# tps62130.net
KiCad netlist of a schematic drawn in Altium Designer
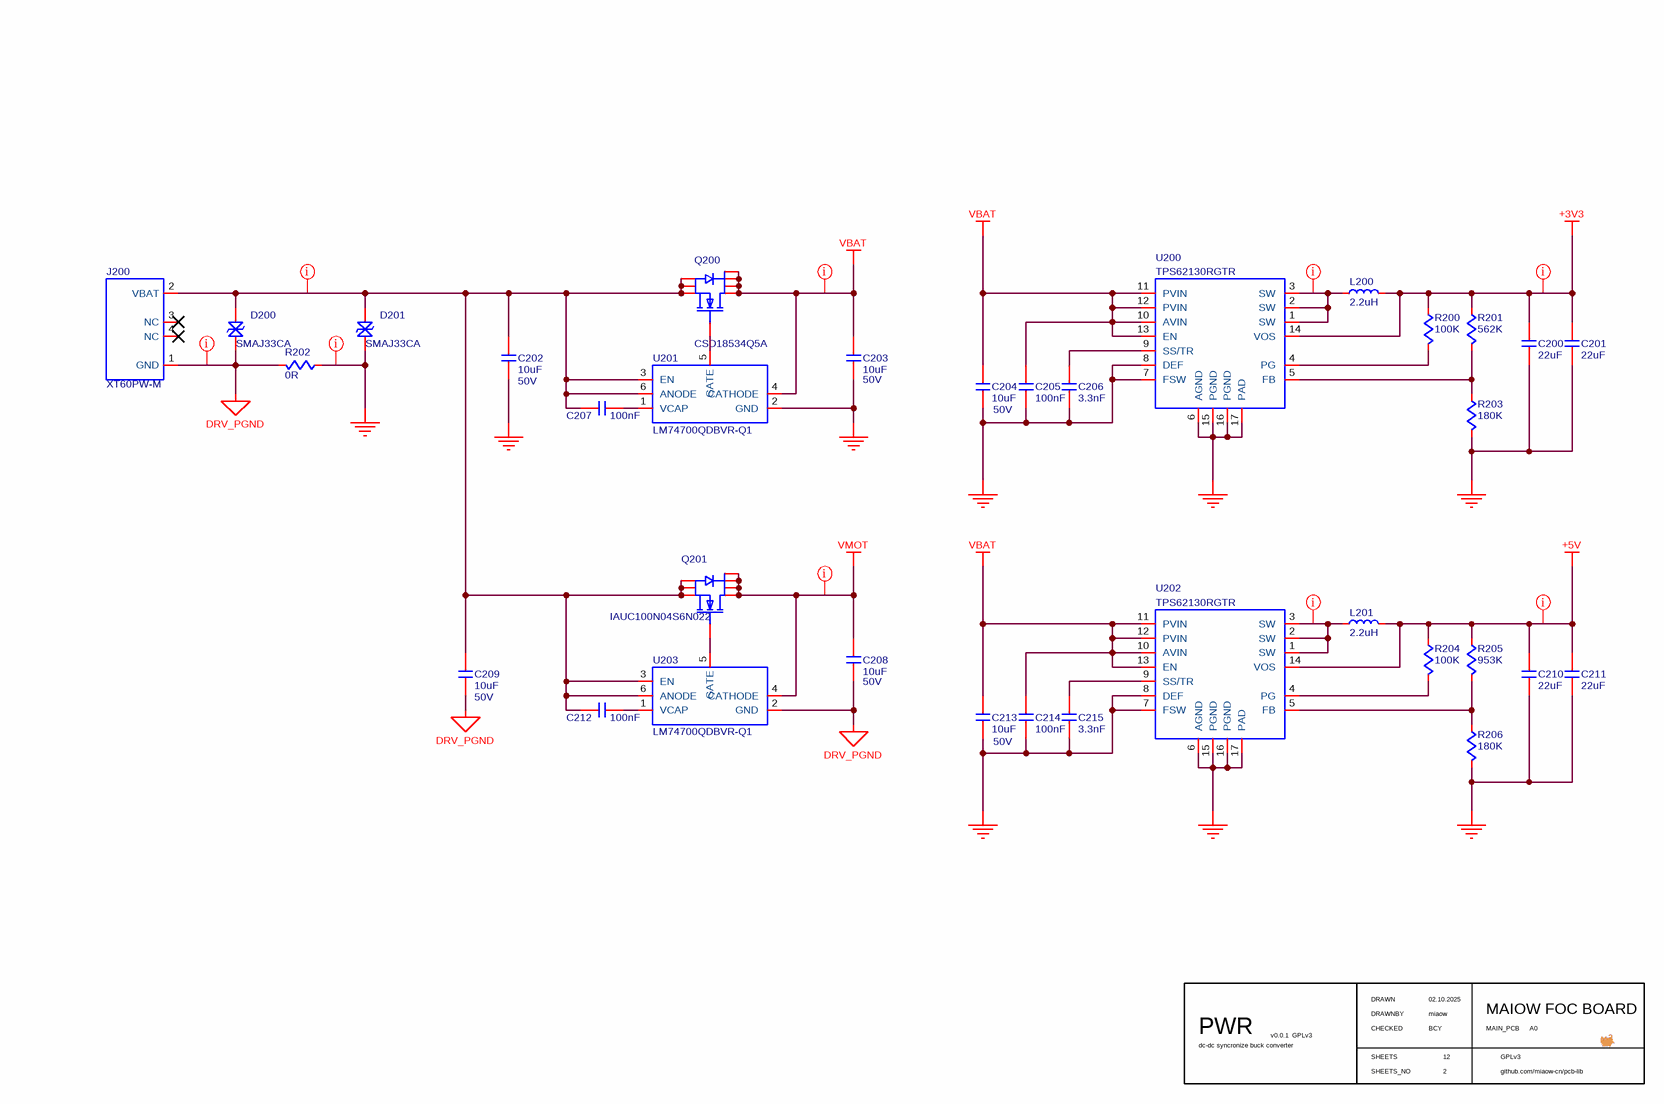
[diagram p0: tps62130.SchDoc]

(export (version "E")
  (design (tool "Eeschema 10.0.6"))
  (components
    (comp (ref "C200")
      (value "22uF")
      (footprint "mw:C0805")
      (fields (field (name "VOLTAGE") "25V") (field (name "Comment") "C-NOMO"))
      (libsource (lib "mw") (part "C-NOMO"))
    )
    (comp (ref "C201")
      (value "22uF")
      (footprint "mw:C0805")
      (fields (field (name "VOLTAGE") "25V") (field (name "Comment") "C-NOMO"))
      (libsource (lib "mw") (part "C-NOMO"))
    )
    (comp (ref "C202")
      (value "10uF")
      (footprint "mw:C0805")
      (fields (field (name "VOLTAGE") "50V") (field (name "Comment") "C-NOMO"))
      (libsource (lib "mw") (part "C-NOMO"))
    )
    (comp (ref "C203")
      (value "10uF")
      (footprint "mw:C0805")
      (fields (field (name "VOLTAGE") "50V") (field (name "Comment") "C-NOMO"))
      (libsource (lib "mw") (part "C-NOMO"))
    )
    (comp (ref "C204")
      (value "10uF")
      (footprint "mw:C0805")
      (fields (field (name "VOLTAGE") "50V") (field (name "Comment") "C-NOMO"))
      (libsource (lib "mw") (part "C-NOMO"))
    )
    (comp (ref "C205")
      (value "100nF")
      (footprint "mw:C0603")
      (fields (field (name "VOLTAGE") "25V") (field (name "Comment") "C-NOMO"))
      (libsource (lib "mw") (part "C-NOMO"))
    )
    (comp (ref "C206")
      (value "3.3nF")
      (footprint "mw:C0402")
      (fields (field (name "VOLTAGE") "25V") (field (name "Comment") "C-NOMO"))
      (libsource (lib "mw") (part "C-NOMO"))
    )
    (comp (ref "C207")
      (value "100nF")
      (footprint "mw:C0402")
      (fields (field (name "VOLTAGE") "25V") (field (name "Comment") "C-NOMO"))
      (libsource (lib "mw") (part "C-NOMO"))
    )
    (comp (ref "C208")
      (value "10uF")
      (footprint "mw:C0805")
      (fields (field (name "VOLTAGE") "50V") (field (name "Comment") "C-NOMO"))
      (libsource (lib "mw") (part "C-NOMO"))
    )
    (comp (ref "C209")
      (value "10uF")
      (footprint "mw:C0805")
      (fields (field (name "VOLTAGE") "50V") (field (name "Comment") "C-NOMO"))
      (libsource (lib "mw") (part "C-NOMO"))
    )
    (comp (ref "C210")
      (value "22uF")
      (footprint "mw:C0805")
      (fields (field (name "VOLTAGE") "25V") (field (name "Comment") "C-NOMO"))
      (libsource (lib "mw") (part "C-NOMO"))
    )
    (comp (ref "C211")
      (value "22uF")
      (footprint "mw:C0805")
      (fields (field (name "VOLTAGE") "25V") (field (name "Comment") "C-NOMO"))
      (libsource (lib "mw") (part "C-NOMO"))
    )
    (comp (ref "C212")
      (value "100nF")
      (footprint "mw:C0402")
      (fields (field (name "VOLTAGE") "25V") (field (name "Comment") "C-NOMO"))
      (libsource (lib "mw") (part "C-NOMO"))
    )
    (comp (ref "C213")
      (value "10uF")
      (footprint "mw:C0805")
      (fields (field (name "VOLTAGE") "50V") (field (name "Comment") "C-NOMO"))
      (libsource (lib "mw") (part "C-NOMO"))
    )
    (comp (ref "C214")
      (value "100nF")
      (footprint "mw:C0603")
      (fields (field (name "VOLTAGE") "25V") (field (name "Comment") "C-NOMO"))
      (libsource (lib "mw") (part "C-NOMO"))
    )
    (comp (ref "C215")
      (value "3.3nF")
      (footprint "mw:C0402")
      (fields (field (name "VOLTAGE") "25V") (field (name "Comment") "C-NOMO"))
      (libsource (lib "mw") (part "C-NOMO"))
    )
    (comp (ref "D200")
      (value "SMAJ33CA")
      (footprint "mw:SMAJ33CA")
      (description "TVS/ESD")
      (libsource (lib "mw") (part "SMAJ33CA"))
    )
    (comp (ref "D201")
      (value "SMAJ33CA")
      (footprint "mw:SMAJ33CA")
      (description "TVS/ESD")
      (libsource (lib "mw") (part "SMAJ33CA"))
    )
    (comp (ref "J200")
      (value "XT60PW-M")
      (footprint "mw:XT60PW-M")
      (description "CONNECTOR - dc supply")
      (libsource (lib "mw") (part "XT60PW-M"))
    )
    (comp (ref "L200")
      (value "2.2uH")
      (footprint "mw:FXL0420")
      (fields (field (name "Comment") "L") (field (name "PUBLISHER") "Altium Limited"))
      (libsource (lib "mw") (part "L"))
    )
    (comp (ref "L201")
      (value "2.2uH")
      (footprint "mw:FXL0420")
      (fields (field (name "Comment") "L") (field (name "PUBLISHER") "Altium Limited"))
      (libsource (lib "mw") (part "L"))
    )
    (comp (ref "Q200")
      (value "CSD18534Q5A")
      (footprint "mw:CSD18534Q5A")
      (description "NMOS")
      (libsource (lib "mw") (part "CSD18534Q5A"))
    )
    (comp (ref "Q201")
      (value "IAUC100N04S6N022")
      (footprint "mw:IAUC100N04S6N022")
      (description "NMOS")
      (libsource (lib "mw") (part "IAUC100N04S6N022"))
    )
    (comp (ref "R200")
      (value "100K")
      (footprint "mw:R0402")
      (fields (field (name "Comment") "R"))
      (libsource (lib "mw") (part "R"))
    )
    (comp (ref "R201")
      (value "562K")
      (footprint "mw:R0603")
      (fields (field (name "Comment") "R"))
      (libsource (lib "mw") (part "R"))
    )
    (comp (ref "R202")
      (value "0R")
      (footprint "mw:R1206")
      (fields (field (name "Comment") "R"))
      (libsource (lib "mw") (part "R"))
    )
    (comp (ref "R203")
      (value "180K")
      (footprint "mw:R0603")
      (fields (field (name "Comment") "R"))
      (libsource (lib "mw") (part "R"))
    )
    (comp (ref "R204")
      (value "100K")
      (footprint "mw:R0402")
      (fields (field (name "Comment") "R"))
      (libsource (lib "mw") (part "R"))
    )
    (comp (ref "R205")
      (value "953K")
      (footprint "mw:R0603")
      (fields (field (name "Comment") "R"))
      (libsource (lib "mw") (part "R"))
    )
    (comp (ref "R206")
      (value "180K")
      (footprint "mw:R0603")
      (fields (field (name "Comment") "R"))
      (libsource (lib "mw") (part "R"))
    )
    (comp (ref "U200")
      (value "TPS62130RGTR")
      (footprint "mw:TPS62130RGTR")
      (libsource (lib "mw") (part "TPS62130RGTR"))
    )
    (comp (ref "U201")
      (value "LM74700QDBVR-Q1")
      (footprint "mw:LM74700QDBVR-Q1")
      (description "IDEAL DIODE")
      (libsource (lib "mw") (part "LM74700QDBVR-Q1"))
    )
    (comp (ref "U202")
      (value "TPS62130RGTR")
      (footprint "mw:TPS62130RGTR")
      (libsource (lib "mw") (part "TPS62130RGTR"))
    )
    (comp (ref "U203")
      (value "LM74700QDBVR-Q1")
      (footprint "mw:LM74700QDBVR-Q1")
      (description "IDEAL DIODE")
      (libsource (lib "mw") (part "LM74700QDBVR-Q1"))
    )
  )
  (nets
    (net (code "1") (name "+3V3") (class "Default")
      (node (ref "C200") (pin "2") (pinfunction "2_2") (pintype "passive"))
      (node (ref "C201") (pin "2") (pinfunction "2_2") (pintype "passive"))
      (node (ref "L200") (pin "2") (pinfunction "2_2") (pintype "passive"))
      (node (ref "R200") (pin "2") (pinfunction "2_2") (pintype "passive"))
      (node (ref "R201") (pin "2") (pinfunction "2_2") (pintype "passive"))
      (node (ref "U200") (pin "14") (pinfunction "VOS_14") (pintype "passive"))
    )
    (net (code "2") (name "+5V") (class "Default")
      (node (ref "C210") (pin "2") (pinfunction "2_2") (pintype "passive"))
      (node (ref "C211") (pin "2") (pinfunction "2_2") (pintype "passive"))
      (node (ref "L201") (pin "2") (pinfunction "2_2") (pintype "passive"))
      (node (ref "R204") (pin "2") (pinfunction "2_2") (pintype "passive"))
      (node (ref "R205") (pin "2") (pinfunction "2_2") (pintype "passive"))
      (node (ref "U202") (pin "14") (pinfunction "VOS_14") (pintype "passive"))
    )
    (net (code "3") (name "DRV_PGND") (class "Default")
      (node (ref "C208") (pin "1") (pinfunction "1_1") (pintype "passive"))
      (node (ref "C209") (pin "1") (pinfunction "1_1") (pintype "passive"))
      (node (ref "D200") (pin "1") (pinfunction "1_1") (pintype "passive"))
      (node (ref "J200") (pin "1") (pinfunction "GND_1") (pintype "passive"))
      (node (ref "R202") (pin "1") (pinfunction "1_1") (pintype "passive"))
      (node (ref "U203") (pin "2") (pinfunction "GND_2") (pintype "passive"))
    )
    (net (code "4") (name "GND") (class "Default")
      (node (ref "C200") (pin "1") (pinfunction "1_1") (pintype "passive"))
      (node (ref "C201") (pin "1") (pinfunction "1_1") (pintype "passive"))
      (node (ref "C202") (pin "1") (pinfunction "1_1") (pintype "passive"))
      (node (ref "C203") (pin "1") (pinfunction "1_1") (pintype "passive"))
      (node (ref "C204") (pin "1") (pinfunction "1_1") (pintype "passive"))
      (node (ref "C205") (pin "1") (pinfunction "1_1") (pintype "passive"))
      (node (ref "C206") (pin "1") (pinfunction "1_1") (pintype "passive"))
      (node (ref "C210") (pin "1") (pinfunction "1_1") (pintype "passive"))
      (node (ref "C211") (pin "1") (pinfunction "1_1") (pintype "passive"))
      (node (ref "C213") (pin "1") (pinfunction "1_1") (pintype "passive"))
      (node (ref "C214") (pin "1") (pinfunction "1_1") (pintype "passive"))
      (node (ref "C215") (pin "1") (pinfunction "1_1") (pintype "passive"))
      (node (ref "D201") (pin "1") (pinfunction "1_1") (pintype "passive"))
      (node (ref "R202") (pin "2") (pinfunction "2_2") (pintype "passive"))
      (node (ref "R203") (pin "1") (pinfunction "1_1") (pintype "passive"))
      (node (ref "R206") (pin "1") (pinfunction "1_1") (pintype "passive"))
      (node (ref "U200") (pin "15") (pinfunction "PGND_15") (pintype "passive"))
      (node (ref "U200") (pin "16") (pinfunction "PGND_16") (pintype "passive"))
      (node (ref "U200") (pin "17") (pinfunction "PAD_17") (pintype "passive"))
      (node (ref "U200") (pin "6") (pinfunction "AGND_6") (pintype "passive"))
      (node (ref "U200") (pin "7") (pinfunction "FSW_7") (pintype "passive"))
      (node (ref "U200") (pin "8") (pinfunction "DEF_8") (pintype "passive"))
      (node (ref "U201") (pin "2") (pinfunction "GND_2") (pintype "passive"))
      (node (ref "U202") (pin "15") (pinfunction "PGND_15") (pintype "passive"))
      (node (ref "U202") (pin "16") (pinfunction "PGND_16") (pintype "passive"))
      (node (ref "U202") (pin "17") (pinfunction "PAD_17") (pintype "passive"))
      (node (ref "U202") (pin "6") (pinfunction "AGND_6") (pintype "passive"))
      (node (ref "U202") (pin "7") (pinfunction "FSW_7") (pintype "passive"))
      (node (ref "U202") (pin "8") (pinfunction "DEF_8") (pintype "passive"))
    )
    (net (code "5") (name "Net-(J200-VBAT)") (class "Default")
      (node (ref "C202") (pin "2") (pinfunction "2_2") (pintype "passive"))
      (node (ref "C207") (pin "1") (pinfunction "1_1") (pintype "passive"))
      (node (ref "C209") (pin "2") (pinfunction "2_2") (pintype "passive"))
      (node (ref "C212") (pin "1") (pinfunction "1_1") (pintype "passive"))
      (node (ref "D200") (pin "2") (pinfunction "2_2") (pintype "passive"))
      (node (ref "D201") (pin "2") (pinfunction "2_2") (pintype "passive"))
      (node (ref "J200") (pin "2") (pinfunction "VBAT_2") (pintype "passive"))
      (node (ref "Q200") (pin "1") (pinfunction "S_1") (pintype "passive"))
      (node (ref "Q200") (pin "2") (pinfunction "S_2") (pintype "passive"))
      (node (ref "Q200") (pin "3") (pinfunction "S_3") (pintype "passive"))
      (node (ref "Q201") (pin "1") (pinfunction "S_1") (pintype "passive"))
      (node (ref "Q201") (pin "2") (pinfunction "S_2") (pintype "passive"))
      (node (ref "Q201") (pin "3") (pinfunction "S_3") (pintype "passive"))
      (node (ref "U201") (pin "3") (pinfunction "EN_3") (pintype "passive"))
      (node (ref "U201") (pin "6") (pinfunction "ANODE_6") (pintype "passive"))
      (node (ref "U203") (pin "3") (pinfunction "EN_3") (pintype "passive"))
      (node (ref "U203") (pin "6") (pinfunction "ANODE_6") (pintype "passive"))
    )
    (net (code "6") (name "Net-(L200-Pad1)") (class "Default")
      (node (ref "L200") (pin "1") (pinfunction "1_1") (pintype "passive"))
      (node (ref "U200") (pin "1") (pinfunction "SW_1") (pintype "passive"))
      (node (ref "U200") (pin "2") (pinfunction "SW_2") (pintype "passive"))
      (node (ref "U200") (pin "3") (pinfunction "SW_3") (pintype "passive"))
    )
    (net (code "7") (name "Net-(L201-Pad1)") (class "Default")
      (node (ref "L201") (pin "1") (pinfunction "1_1") (pintype "passive"))
      (node (ref "U202") (pin "1") (pinfunction "SW_1") (pintype "passive"))
      (node (ref "U202") (pin "2") (pinfunction "SW_2") (pintype "passive"))
      (node (ref "U202") (pin "3") (pinfunction "SW_3") (pintype "passive"))
    )
    (net (code "8") (name "Net-(Q200-G)") (class "Default")
      (node (ref "Q200") (pin "4") (pinfunction "G_4") (pintype "passive"))
      (node (ref "U201") (pin "5") (pinfunction "GATE_5") (pintype "passive"))
    )
    (net (code "9") (name "Net-(Q201-G)") (class "Default")
      (node (ref "Q201") (pin "4") (pinfunction "G_4") (pintype "passive"))
      (node (ref "U203") (pin "5") (pinfunction "GATE_5") (pintype "passive"))
    )
    (net (code "10") (name "Net-(U200-FB)") (class "Default")
      (node (ref "R201") (pin "1") (pinfunction "1_1") (pintype "passive"))
      (node (ref "R203") (pin "2") (pinfunction "2_2") (pintype "passive"))
      (node (ref "U200") (pin "5") (pinfunction "FB_5") (pintype "passive"))
    )
    (net (code "11") (name "Net-(U200-PG)") (class "Default")
      (node (ref "R200") (pin "1") (pinfunction "1_1") (pintype "passive"))
      (node (ref "U200") (pin "4") (pinfunction "PG_4") (pintype "passive"))
    )
    (net (code "12") (name "Net-(U200-SS{slash}TR)") (class "Default")
      (node (ref "C206") (pin "2") (pinfunction "2_2") (pintype "passive"))
      (node (ref "U200") (pin "9") (pinfunction "SS/TR_9") (pintype "passive"))
    )
    (net (code "13") (name "Net-(U201-VCAP)") (class "Default")
      (node (ref "C207") (pin "2") (pinfunction "2_2") (pintype "passive"))
      (node (ref "U201") (pin "1") (pinfunction "VCAP_1") (pintype "passive"))
    )
    (net (code "14") (name "Net-(U202-FB)") (class "Default")
      (node (ref "R205") (pin "1") (pinfunction "1_1") (pintype "passive"))
      (node (ref "R206") (pin "2") (pinfunction "2_2") (pintype "passive"))
      (node (ref "U202") (pin "5") (pinfunction "FB_5") (pintype "passive"))
    )
    (net (code "15") (name "Net-(U202-PG)") (class "Default")
      (node (ref "R204") (pin "1") (pinfunction "1_1") (pintype "passive"))
      (node (ref "U202") (pin "4") (pinfunction "PG_4") (pintype "passive"))
    )
    (net (code "16") (name "Net-(U202-SS{slash}TR)") (class "Default")
      (node (ref "C215") (pin "2") (pinfunction "2_2") (pintype "passive"))
      (node (ref "U202") (pin "9") (pinfunction "SS/TR_9") (pintype "passive"))
    )
    (net (code "17") (name "Net-(U203-VCAP)") (class "Default")
      (node (ref "C212") (pin "2") (pinfunction "2_2") (pintype "passive"))
      (node (ref "U203") (pin "1") (pinfunction "VCAP_1") (pintype "passive"))
    )
    (net (code "18") (name "VBAT") (class "Default")
      (node (ref "C203") (pin "2") (pinfunction "2_2") (pintype "passive"))
      (node (ref "C204") (pin "2") (pinfunction "2_2") (pintype "passive"))
      (node (ref "C205") (pin "2") (pinfunction "2_2") (pintype "passive"))
      (node (ref "C213") (pin "2") (pinfunction "2_2") (pintype "passive"))
      (node (ref "C214") (pin "2") (pinfunction "2_2") (pintype "passive"))
      (node (ref "Q200") (pin "5") (pinfunction "D_5") (pintype "passive"))
      (node (ref "Q200") (pin "6") (pinfunction "D_6") (pintype "passive"))
      (node (ref "Q200") (pin "7") (pinfunction "D_7") (pintype "passive"))
      (node (ref "Q200") (pin "8") (pinfunction "D_8") (pintype "passive"))
      (node (ref "U200") (pin "10") (pinfunction "AVIN_10") (pintype "passive"))
      (node (ref "U200") (pin "11") (pinfunction "PVIN_11") (pintype "passive"))
      (node (ref "U200") (pin "12") (pinfunction "PVIN_12") (pintype "passive"))
      (node (ref "U200") (pin "13") (pinfunction "EN_13") (pintype "passive"))
      (node (ref "U201") (pin "4") (pinfunction "CATHODE_4") (pintype "passive"))
      (node (ref "U202") (pin "10") (pinfunction "AVIN_10") (pintype "passive"))
      (node (ref "U202") (pin "11") (pinfunction "PVIN_11") (pintype "passive"))
      (node (ref "U202") (pin "12") (pinfunction "PVIN_12") (pintype "passive"))
      (node (ref "U202") (pin "13") (pinfunction "EN_13") (pintype "passive"))
    )
    (net (code "19") (name "VMOT") (class "Default")
      (node (ref "C208") (pin "2") (pinfunction "2_2") (pintype "passive"))
      (node (ref "Q201") (pin "5") (pinfunction "D_5") (pintype "passive"))
      (node (ref "Q201") (pin "6") (pinfunction "D_6") (pintype "passive"))
      (node (ref "Q201") (pin "7") (pinfunction "D_7") (pintype "passive"))
      (node (ref "Q201") (pin "8") (pinfunction "D_8") (pintype "passive"))
      (node (ref "U203") (pin "4") (pinfunction "CATHODE_4") (pintype "passive"))
    )
    (net (code "20") (name "unconnected-(J200-NC-Pad3)") (class "Default")
      (node (ref "J200") (pin "3") (pinfunction "NC_3") (pintype "passive+no_connect"))
    )
    (net (code "21") (name "unconnected-(J200-NC-Pad4)") (class "Default")
      (node (ref "J200") (pin "4") (pinfunction "NC_4") (pintype "passive+no_connect"))
    )
  )
)
